# BUFFER.net
KiCad netlist of a schematic drawn in Altium Designer
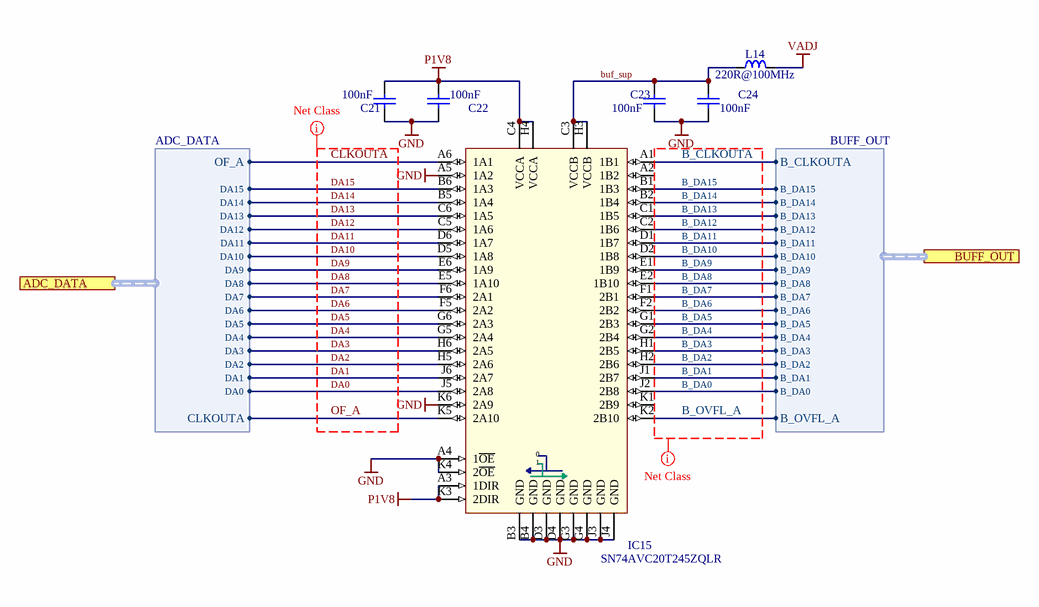
[diagram p0: BUFFER.SchDoc]

(export (version "E")
  (design (tool "Eeschema 10.0.6"))
  (components
    (comp (ref "C21")
      (value "100nF")
      (footprint "CAPC0603X33N")
      (description "Non-polarised capacitor")
      (fields
        (field (name "PART NUMBER") "CC0201_100NF_6.3V_10%_X5R")
        (field (name "VOLTAGE") "6.3V")
        (field (name "AUTHOR") "CERN DEM JLC")
      )
      (libsource (lib "Capacitors") (part "Capacitor - non polarized"))
    )
    (comp (ref "C22")
      (value "100nF")
      (footprint "CAPC0603X33N")
      (description "Non-polarised capacitor")
      (fields
        (field (name "PART NUMBER") "CC0201_100NF_6.3V_10%_X5R")
        (field (name "VOLTAGE") "6.3V")
        (field (name "AUTHOR") "CERN DEM JLC")
      )
      (libsource (lib "Capacitors") (part "Capacitor - non polarized"))
    )
    (comp (ref "C23")
      (value "100nF")
      (footprint "CAPC0603X33N")
      (description "Non-polarised capacitor")
      (fields
        (field (name "PART NUMBER") "CC0201_100NF_6.3V_10%_X5R")
        (field (name "VOLTAGE") "6.3V")
        (field (name "AUTHOR") "CERN DEM JLC")
      )
      (libsource (lib "Capacitors") (part "Capacitor - non polarized"))
    )
    (comp (ref "C24")
      (value "100nF")
      (footprint "CAPC0603X33N")
      (description "Non-polarised capacitor")
      (fields
        (field (name "PART NUMBER") "CC0201_100NF_6.3V_10%_X5R")
        (field (name "VOLTAGE") "6.3V")
        (field (name "AUTHOR") "CERN DEM JLC")
      )
      (libsource (lib "Capacitors") (part "Capacitor - non polarized"))
    )
    (comp (ref "IC15")
      (value "SN74AVC20T245ZQLR")
      (footprint "ZQL56(R-PBGA-N56)")
      (description "20-BIT DUAL SUPPLY BUS TRANSCEIVER")
      (libsource (lib "LIBRARY_SCH") (part "74AVC20T245"))
    )
    (comp (ref "L14")
      (value "220R@100MHz")
      (footprint "INDC2012X105N")
      (description "Inductor")
      (fields
        (field (name "PART NUMBER") "IND0805_MURATA_BLM21PG221SN1D")
        (field (name "POWER") "2A")
        (field (name "AUTHOR") "CERN DEM JLC")
      )
      (libsource (lib "Inductors & Transformers") (part "Inductor"))
    )
  )
  (nets
    (net (code "3") (name "/B_CLKOUTA") (class "Default")
      (node (ref "IC15") (pin "A1") (pinfunction "1B1_A1") (pintype "bidirectional"))
    )
    (net (code "4") (name "/B_DA0") (class "Default")
      (node (ref "IC15") (pin "J2") (pinfunction "2B8_J2") (pintype "bidirectional"))
    )
    (net (code "5") (name "/B_DA1") (class "Default")
      (node (ref "IC15") (pin "J1") (pinfunction "2B7_J1") (pintype "bidirectional"))
    )
    (net (code "6") (name "/B_DA2") (class "Default")
      (node (ref "IC15") (pin "H2") (pinfunction "2B6_H2") (pintype "bidirectional"))
    )
    (net (code "7") (name "/B_DA3") (class "Default")
      (node (ref "IC15") (pin "H1") (pinfunction "2B5_H1") (pintype "bidirectional"))
    )
    (net (code "8") (name "/B_DA4") (class "Default")
      (node (ref "IC15") (pin "G2") (pinfunction "2B4_G2") (pintype "bidirectional"))
    )
    (net (code "9") (name "/B_DA5") (class "Default")
      (node (ref "IC15") (pin "G1") (pinfunction "2B3_G1") (pintype "bidirectional"))
    )
    (net (code "10") (name "/B_DA6") (class "Default")
      (node (ref "IC15") (pin "F2") (pinfunction "2B2_F2") (pintype "bidirectional"))
    )
    (net (code "11") (name "/B_DA7") (class "Default")
      (node (ref "IC15") (pin "F1") (pinfunction "2B1_F1") (pintype "bidirectional"))
    )
    (net (code "12") (name "/B_DA8") (class "Default")
      (node (ref "IC15") (pin "E2") (pinfunction "1B10_E2") (pintype "bidirectional"))
    )
    (net (code "13") (name "/B_DA9") (class "Default")
      (node (ref "IC15") (pin "E1") (pinfunction "1B9_E1") (pintype "bidirectional"))
    )
    (net (code "14") (name "/B_DA10") (class "Default")
      (node (ref "IC15") (pin "D2") (pinfunction "1B8_D2") (pintype "bidirectional"))
    )
    (net (code "15") (name "/B_DA11") (class "Default")
      (node (ref "IC15") (pin "D1") (pinfunction "1B7_D1") (pintype "bidirectional"))
    )
    (net (code "16") (name "/B_DA12") (class "Default")
      (node (ref "IC15") (pin "C2") (pinfunction "1B6_C2") (pintype "bidirectional"))
    )
    (net (code "17") (name "/B_DA13") (class "Default")
      (node (ref "IC15") (pin "C1") (pinfunction "1B5_C1") (pintype "bidirectional"))
    )
    (net (code "18") (name "/B_DA14") (class "Default")
      (node (ref "IC15") (pin "B2") (pinfunction "1B4_B2") (pintype "bidirectional"))
    )
    (net (code "19") (name "/B_DA15") (class "Default")
      (node (ref "IC15") (pin "B1") (pinfunction "1B3_B1") (pintype "bidirectional"))
    )
    (net (code "20") (name "/B_OVFL_A") (class "Default")
      (node (ref "IC15") (pin "K2") (pinfunction "2B10_K2") (pintype "bidirectional"))
    )
    (net (code "21") (name "/CLKOUTA") (class "Default")
      (node (ref "IC15") (pin "A6") (pinfunction "1A1_A6") (pintype "bidirectional"))
    )
    (net (code "22") (name "/DA0") (class "Default")
      (node (ref "IC15") (pin "J5") (pinfunction "2A8_J5") (pintype "bidirectional"))
    )
    (net (code "23") (name "/DA1") (class "Default")
      (node (ref "IC15") (pin "J6") (pinfunction "2A7_J6") (pintype "bidirectional"))
    )
    (net (code "24") (name "/DA2") (class "Default")
      (node (ref "IC15") (pin "H5") (pinfunction "2A6_H5") (pintype "bidirectional"))
    )
    (net (code "25") (name "/DA3") (class "Default")
      (node (ref "IC15") (pin "H6") (pinfunction "2A5_H6") (pintype "bidirectional"))
    )
    (net (code "26") (name "/DA4") (class "Default")
      (node (ref "IC15") (pin "G5") (pinfunction "2A4_G5") (pintype "bidirectional"))
    )
    (net (code "27") (name "/DA5") (class "Default")
      (node (ref "IC15") (pin "G6") (pinfunction "2A3_G6") (pintype "bidirectional"))
    )
    (net (code "28") (name "/DA6") (class "Default")
      (node (ref "IC15") (pin "F5") (pinfunction "2A2_F5") (pintype "bidirectional"))
    )
    (net (code "29") (name "/DA7") (class "Default")
      (node (ref "IC15") (pin "F6") (pinfunction "2A1_F6") (pintype "bidirectional"))
    )
    (net (code "30") (name "/DA8") (class "Default")
      (node (ref "IC15") (pin "E5") (pinfunction "1A10_E5") (pintype "bidirectional"))
    )
    (net (code "31") (name "/DA9") (class "Default")
      (node (ref "IC15") (pin "E6") (pinfunction "1A9_E6") (pintype "bidirectional"))
    )
    (net (code "32") (name "/DA10") (class "Default")
      (node (ref "IC15") (pin "D5") (pinfunction "1A8_D5") (pintype "bidirectional"))
    )
    (net (code "33") (name "/DA11") (class "Default")
      (node (ref "IC15") (pin "D6") (pinfunction "1A7_D6") (pintype "bidirectional"))
    )
    (net (code "34") (name "/DA12") (class "Default")
      (node (ref "IC15") (pin "C5") (pinfunction "1A6_C5") (pintype "bidirectional"))
    )
    (net (code "35") (name "/DA13") (class "Default")
      (node (ref "IC15") (pin "C6") (pinfunction "1A5_C6") (pintype "bidirectional"))
    )
    (net (code "36") (name "/DA14") (class "Default")
      (node (ref "IC15") (pin "B5") (pinfunction "1A4_B5") (pintype "bidirectional"))
    )
    (net (code "37") (name "/DA15") (class "Default")
      (node (ref "IC15") (pin "B6") (pinfunction "1A3_B6") (pintype "bidirectional"))
    )
    (net (code "38") (name "/OF_A") (class "Default")
      (node (ref "IC15") (pin "K5") (pinfunction "2A10_K5") (pintype "bidirectional"))
    )
    (net (code "39") (name "/buf_sup") (class "Default")
      (node (ref "C23") (pin "2") (pinfunction "2_2") (pintype "passive"))
      (node (ref "C24") (pin "2") (pinfunction "2_2") (pintype "passive"))
      (node (ref "IC15") (pin "C3") (pinfunction "VCCB_C3") (pintype "power_in"))
      (node (ref "IC15") (pin "H3") (pinfunction "VCCB_H3") (pintype "power_in"))
      (node (ref "L14") (pin "1") (pinfunction "1_1") (pintype "passive"))
    )
    (net (code "42") (name "GND") (class "Default")
      (node (ref "C21") (pin "1") (pinfunction "1_1") (pintype "passive"))
      (node (ref "C22") (pin "1") (pinfunction "1_1") (pintype "passive"))
      (node (ref "C23") (pin "1") (pinfunction "1_1") (pintype "passive"))
      (node (ref "C24") (pin "1") (pinfunction "1_1") (pintype "passive"))
      (node (ref "IC15") (pin "A4") (pinfunction "1~{OE}_A4") (pintype "input"))
      (node (ref "IC15") (pin "A5") (pinfunction "1A2_A5") (pintype "bidirectional"))
      (node (ref "IC15") (pin "B3") (pinfunction "GND_B3") (pintype "power_in"))
      (node (ref "IC15") (pin "B4") (pinfunction "GND_B4") (pintype "power_in"))
      (node (ref "IC15") (pin "D3") (pinfunction "GND_D3") (pintype "power_in"))
      (node (ref "IC15") (pin "D4") (pinfunction "GND_D4") (pintype "power_in"))
      (node (ref "IC15") (pin "G3") (pinfunction "GND_G3") (pintype "power_in"))
      (node (ref "IC15") (pin "G4") (pinfunction "GND_G4") (pintype "power_in"))
      (node (ref "IC15") (pin "J3") (pinfunction "GND_J3") (pintype "power_in"))
      (node (ref "IC15") (pin "J4") (pinfunction "GND_J4") (pintype "power_in"))
      (node (ref "IC15") (pin "K4") (pinfunction "2~{OE}_K4") (pintype "input"))
      (node (ref "IC15") (pin "K6") (pinfunction "2A9_K6") (pintype "bidirectional"))
    )
    (net (code "43") (name "P1V8") (class "Default")
      (node (ref "C21") (pin "2") (pinfunction "2_2") (pintype "passive"))
      (node (ref "C22") (pin "2") (pinfunction "2_2") (pintype "passive"))
      (node (ref "IC15") (pin "A3") (pinfunction "1DIR_A3") (pintype "input"))
      (node (ref "IC15") (pin "C4") (pinfunction "VCCA_C4") (pintype "power_in"))
      (node (ref "IC15") (pin "H4") (pinfunction "VCCA_H4") (pintype "power_in"))
      (node (ref "IC15") (pin "K3") (pinfunction "2DIR_K3") (pintype "input"))
    )
    (net (code "44") (name "VADJ") (class "Default")
      (node (ref "L14") (pin "2") (pinfunction "2_2") (pintype "passive"))
    )
    (net (code "45") (name "unconnected-(IC15-1B2-PadA2)") (class "Default")
      (node (ref "IC15") (pin "A2") (pinfunction "1B2_A2") (pintype "bidirectional"))
    )
    (net (code "46") (name "unconnected-(IC15-2B9-PadK1)") (class "Default")
      (node (ref "IC15") (pin "K1") (pinfunction "2B9_K1") (pintype "bidirectional"))
    )
  )
)
